# SPSTrelay_w_diodes.net
KiCad netlist of a schematic drawn in EAGLE
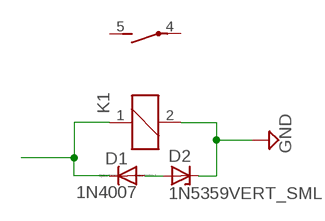
[diagram p0: schematic, sheet 1]

(export (version "E")
  (design (tool "Eeschema 10.0.6"))
  (components
    (comp (ref "D1")
      (value "1N4007")
      (footprint "eagle-import:RAD2,5")
      (libsource (lib "eagle-import") (part "1N4007"))
    )
    (comp (ref "D2")
      (value "1N5359VERT_SML")
      (footprint "eagle-import:RAD2.5_D2")
      (libsource (lib "eagle-import") (part "1N5359VERT_SML"))
    )
    (comp (ref "K1")
      (value "HF41F-12-H")
      (footprint "eagle-import:HF41F-12-H")
      (libsource (lib "eagle-import") (part "HF41F-12-H"))
    )
  )
  (nets
    (net (code "1") (name "GND") (class "Default")
      (node (ref "D2") (pin "C") (pinfunction "C_C") (pintype "passive"))
      (node (ref "K1") (pin "2") (pinfunction "2_2") (pintype "passive"))
    )
    (net (code "2") (name "Net-(D1-PadA)") (class "Default")
      (node (ref "D1") (pin "A") (pinfunction "A_A") (pintype "passive"))
      (node (ref "D2") (pin "A") (pinfunction "A_A") (pintype "passive"))
    )
    (net (code "3") (name "Net-(D1-PadC)") (class "Default")
      (node (ref "D1") (pin "C") (pinfunction "C_C") (pintype "passive"))
      (node (ref "K1") (pin "1") (pinfunction "1_1") (pintype "passive"))
    )
    (net (code "4") (name "unconnected-(K1B-P-Pad4)") (class "Default")
      (node (ref "K1") (pin "4") (pinfunction "P_4") (pintype "passive"))
    )
    (net (code "5") (name "unconnected-(K1B-S-Pad5)") (class "Default")
      (node (ref "K1") (pin "5") (pinfunction "S_5") (pintype "passive"))
    )
  )
)
